# SCH.net
KiCad netlist of a schematic drawn in Altium Designer
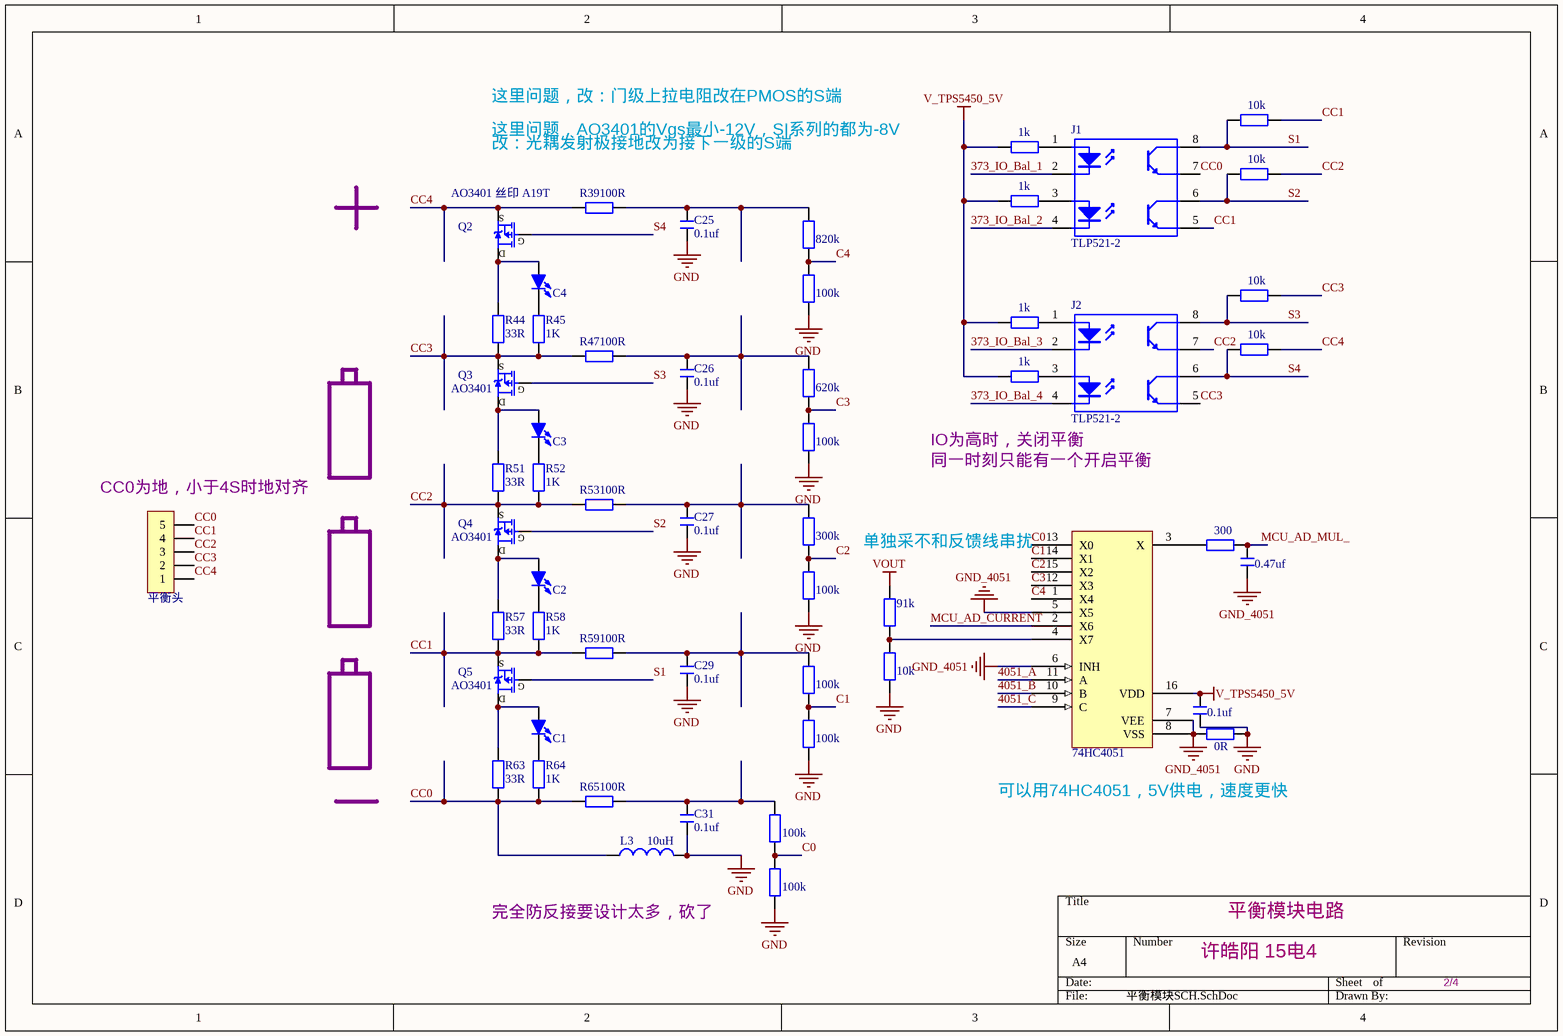
[diagram p0: 平衡模块SCH.SchDoc]

(export (version "E")
  (design (tool "Eeschema 10.0.6"))
  (components
    (comp (ref "*1") (value "74HC4051") (footprint "SOP16_N") (libsource (lib "IC_temp") (part "CD4051")))
    (comp (ref "11")
      (value "91k")
      (footprint "R 0805_M")
      (description "贴片电阻")
      (libsource (lib "3.1   - 电阻-电容-电感") (part "R"))
    )
    (comp (ref "12")
      (value "10k")
      (footprint "R 0805_M")
      (description "贴片电阻")
      (libsource (lib "3.1   - 电阻-电容-电感") (part "R"))
    )
    (comp (ref "C25")
      (value "0.1uf")
      (footprint "C 0805_M")
      (description "无极性贴片电容")
      (libsource (lib "3.1   - 电阻-电容-电感") (part "C"))
    )
    (comp (ref "C26")
      (value "0.1uf")
      (footprint "C 0805_M")
      (description "无极性贴片电容")
      (libsource (lib "3.1   - 电阻-电容-电感") (part "C"))
    )
    (comp (ref "C27")
      (value "0.1uf")
      (footprint "C 0805_M")
      (description "无极性贴片电容")
      (libsource (lib "3.1   - 电阻-电容-电感") (part "C"))
    )
    (comp (ref "C28")
      (value "0.47uf")
      (footprint "C 0805_M")
      (description "无极性贴片电容")
      (libsource (lib "3.1   - 电阻-电容-电感") (part "C"))
    )
    (comp (ref "C29")
      (value "0.1uf")
      (footprint "C 0805_M")
      (description "无极性贴片电容")
      (libsource (lib "3.1   - 电阻-电容-电感") (part "C"))
    )
    (comp (ref "C30")
      (value "0.1uf")
      (footprint "C 0805_M")
      (description "无极性贴片电容")
      (libsource (lib "3.1   - 电阻-电容-电感") (part "C"))
    )
    (comp (ref "C31")
      (value "0.1uf")
      (footprint "C 0805_M")
      (description "无极性贴片电容")
      (libsource (lib "3.1   - 电阻-电容-电感") (part "C"))
    )
    (comp (ref "J1")
      (value "TLP521-2")
      (footprint "SOP8-W2.54_N")
      (description "2路开关光耦")
      (libsource (lib "11.1 - 传感元件") (part "TLP521-2"))
    )
    (comp (ref "J2")
      (value "TLP521-2")
      (footprint "SOP8-W2.54_N")
      (description "2路开关光耦")
      (libsource (lib "11.1 - 传感元件") (part "TLP521-2"))
    )
    (comp (ref "JP9")
      (value "平衡头")
      (footprint "XH2.54-WI-5P")
      (description "5P接插件")
      (libsource (lib "4.6   - 接插件-脚距2.54") (part "Header 5"))
    )
    (comp (ref "L3")
      (value "10uH")
      (footprint "L 0805_M")
      (description "小功率贴片电感")
      (libsource (lib "3.1   - 电阻-电容-电感") (part "L"))
    )
    (comp (ref "LED2")
      (value "C4")
      (footprint "LED 0805G")
      (description "贴片LED")
      (libsource (lib "9.1   - LED") (part "LED-SMD"))
    )
    (comp (ref "LED3")
      (value "C3")
      (footprint "LED 0805G")
      (description "贴片LED")
      (libsource (lib "9.1   - LED") (part "LED-SMD"))
    )
    (comp (ref "LED4")
      (value "C2")
      (footprint "LED 0805G")
      (description "贴片LED")
      (libsource (lib "9.1   - LED") (part "LED-SMD"))
    )
    (comp (ref "LED5")
      (value "C1")
      (footprint "LED 0805G")
      (description "贴片LED")
      (libsource (lib "9.1   - LED") (part "LED-SMD"))
    )
    (comp (ref "Q2")
      (value "AO3401 丝印 A19T")
      (footprint "SOT23-3N")
      (description "P沟道 20V/2.8A")
      (libsource (lib "6.1   - 场效应管-可控硅") (part "SI2301"))
    )
    (comp (ref "Q3")
      (value "AO3401")
      (footprint "SOT23-3N")
      (description "P沟道 20V/2.8A")
      (libsource (lib "6.1   - 场效应管-可控硅") (part "SI2301"))
    )
    (comp (ref "Q4")
      (value "AO3401")
      (footprint "SOT23-3N")
      (description "P沟道 20V/2.8A")
      (libsource (lib "6.1   - 场效应管-可控硅") (part "SI2301"))
    )
    (comp (ref "Q5")
      (value "AO3401")
      (footprint "SOT23-3N")
      (description "P沟道 20V/2.8A")
      (libsource (lib "6.1   - 场效应管-可控硅") (part "SI2301"))
    )
    (comp (ref "R35")
      (value "10k")
      (footprint "R 0805_M")
      (description "贴片电阻")
      (libsource (lib "3.1   - 电阻-电容-电感") (part "R"))
    )
    (comp (ref "R36")
      (value "1k")
      (footprint "R 0805_M")
      (description "贴片电阻")
      (libsource (lib "3.1   - 电阻-电容-电感") (part "R"))
    )
    (comp (ref "R37")
      (value "10k")
      (footprint "R 0805_M")
      (description "贴片电阻")
      (libsource (lib "3.1   - 电阻-电容-电感") (part "R"))
    )
    (comp (ref "R38")
      (value "1k")
      (footprint "R 0805_M")
      (description "贴片电阻")
      (libsource (lib "3.1   - 电阻-电容-电感") (part "R"))
    )
    (comp (ref "R39")
      (value "100R")
      (footprint "R 0805_M")
      (description "贴片电阻")
      (libsource (lib "3.1   - 电阻-电容-电感") (part "R"))
    )
    (comp (ref "R40")
      (value "820k")
      (footprint "R 0805_M")
      (description "贴片电阻")
      (libsource (lib "3.1   - 电阻-电容-电感") (part "R"))
    )
    (comp (ref "R41")
      (value "100k")
      (footprint "R 0805_M")
      (description "贴片电阻")
      (libsource (lib "3.1   - 电阻-电容-电感") (part "R"))
    )
    (comp (ref "R42")
      (value "10k")
      (footprint "R 0805_M")
      (description "贴片电阻")
      (libsource (lib "3.1   - 电阻-电容-电感") (part "R"))
    )
    (comp (ref "R43")
      (value "1k")
      (footprint "R 0805_M")
      (description "贴片电阻")
      (libsource (lib "3.1   - 电阻-电容-电感") (part "R"))
    )
    (comp (ref "R44")
      (value "33R")
      (footprint "R 2512_L")
      (description "贴片电阻")
      (libsource (lib "3.1   - 电阻-电容-电感") (part "R"))
    )
    (comp (ref "R45")
      (value "1K")
      (footprint "R 0805_L")
      (description "贴片电阻")
      (libsource (lib "3.1   - 电阻-电容-电感") (part "R"))
    )
    (comp (ref "R46")
      (value "10k")
      (footprint "R 0805_M")
      (description "贴片电阻")
      (libsource (lib "3.1   - 电阻-电容-电感") (part "R"))
    )
    (comp (ref "R47")
      (value "100R")
      (footprint "R 0805_M")
      (description "贴片电阻")
      (libsource (lib "3.1   - 电阻-电容-电感") (part "R"))
    )
    (comp (ref "R48")
      (value "1k")
      (footprint "R 0805_M")
      (description "贴片电阻")
      (libsource (lib "3.1   - 电阻-电容-电感") (part "R"))
    )
    (comp (ref "R49")
      (value "620k")
      (footprint "R 0805_M")
      (description "贴片电阻")
      (libsource (lib "3.1   - 电阻-电容-电感") (part "R"))
    )
    (comp (ref "R50")
      (value "100k")
      (footprint "R 0805_M")
      (description "贴片电阻")
      (libsource (lib "3.1   - 电阻-电容-电感") (part "R"))
    )
    (comp (ref "R51")
      (value "33R")
      (footprint "R 2512_L")
      (description "贴片电阻")
      (libsource (lib "3.1   - 电阻-电容-电感") (part "R"))
    )
    (comp (ref "R52")
      (value "1K")
      (footprint "R 0805_L")
      (description "贴片电阻")
      (libsource (lib "3.1   - 电阻-电容-电感") (part "R"))
    )
    (comp (ref "R53")
      (value "100R")
      (footprint "R 0805_M")
      (description "贴片电阻")
      (libsource (lib "3.1   - 电阻-电容-电感") (part "R"))
    )
    (comp (ref "R54")
      (value "300k")
      (footprint "R 0805_M")
      (description "贴片电阻")
      (libsource (lib "3.1   - 电阻-电容-电感") (part "R"))
    )
    (comp (ref "R55")
      (value "300")
      (footprint "R 0805_M")
      (description "贴片电阻")
      (libsource (lib "3.1   - 电阻-电容-电感") (part "R"))
    )
    (comp (ref "R56")
      (value "100k")
      (footprint "R 0805_M")
      (description "贴片电阻")
      (libsource (lib "3.1   - 电阻-电容-电感") (part "R"))
    )
    (comp (ref "R57")
      (value "33R")
      (footprint "R 2512_L")
      (description "贴片电阻")
      (libsource (lib "3.1   - 电阻-电容-电感") (part "R"))
    )
    (comp (ref "R58")
      (value "1K")
      (footprint "R 0805_L")
      (description "贴片电阻")
      (libsource (lib "3.1   - 电阻-电容-电感") (part "R"))
    )
    (comp (ref "R59")
      (value "100R")
      (footprint "R 0805_M")
      (description "贴片电阻")
      (libsource (lib "3.1   - 电阻-电容-电感") (part "R"))
    )
    (comp (ref "R60")
      (value "100k")
      (footprint "R 0805_M")
      (description "贴片电阻")
      (libsource (lib "3.1   - 电阻-电容-电感") (part "R"))
    )
    (comp (ref "R61")
      (value "0R")
      (footprint "R 0805_M")
      (description "贴片电阻")
      (libsource (lib "3.1   - 电阻-电容-电感") (part "R"))
    )
    (comp (ref "R62")
      (value "100k")
      (footprint "R 0805_M")
      (description "贴片电阻")
      (libsource (lib "3.1   - 电阻-电容-电感") (part "R"))
    )
    (comp (ref "R63")
      (value "33R")
      (footprint "R 2512_L")
      (description "贴片电阻")
      (libsource (lib "3.1   - 电阻-电容-电感") (part "R"))
    )
    (comp (ref "R64")
      (value "1K")
      (footprint "R 0805_L")
      (description "贴片电阻")
      (libsource (lib "3.1   - 电阻-电容-电感") (part "R"))
    )
    (comp (ref "R65")
      (value "100R")
      (footprint "R 0805_M")
      (description "贴片电阻")
      (libsource (lib "3.1   - 电阻-电容-电感") (part "R"))
    )
    (comp (ref "R66")
      (value "100k")
      (footprint "R 0805_M")
      (description "贴片电阻")
      (libsource (lib "3.1   - 电阻-电容-电感") (part "R"))
    )
    (comp (ref "R67")
      (value "100k")
      (footprint "R 0805_M")
      (description "贴片电阻")
      (libsource (lib "3.1   - 电阻-电容-电感") (part "R"))
    )
  )
  (nets
    (net (code "1") (name "/373_IO_Bal_1") (class "Default")
      (node (ref "J1") (pin "2") (pinfunction "1K_2") (pintype "passive"))
    )
    (net (code "2") (name "/373_IO_Bal_2") (class "Default")
      (node (ref "J1") (pin "4") (pinfunction "2K_4") (pintype "passive"))
    )
    (net (code "3") (name "/373_IO_Bal_3") (class "Default")
      (node (ref "J2") (pin "2") (pinfunction "1K_2") (pintype "passive"))
    )
    (net (code "4") (name "/373_IO_Bal_4") (class "Default")
      (node (ref "J2") (pin "4") (pinfunction "2K_4") (pintype "passive"))
    )
    (net (code "5") (name "/4051_A") (class "Default")
      (node (ref "*1") (pin "11") (pinfunction "A_11") (pintype "input"))
    )
    (net (code "6") (name "/4051_B") (class "Default")
      (node (ref "*1") (pin "10") (pinfunction "B_10") (pintype "input"))
    )
    (net (code "7") (name "/4051_C") (class "Default")
      (node (ref "*1") (pin "9") (pinfunction "C_9") (pintype "input"))
    )
    (net (code "8") (name "/C0") (class "Default")
      (node (ref "*1") (pin "13") (pinfunction "X0_13") (pintype "passive"))
      (node (ref "R66") (pin "2") (pinfunction "2_2") (pintype "passive"))
      (node (ref "R67") (pin "1") (pinfunction "1_1") (pintype "passive"))
    )
    (net (code "9") (name "/C1") (class "Default")
      (node (ref "*1") (pin "14") (pinfunction "X1_14") (pintype "passive"))
      (node (ref "R60") (pin "2") (pinfunction "2_2") (pintype "passive"))
      (node (ref "R62") (pin "1") (pinfunction "1_1") (pintype "passive"))
    )
    (net (code "10") (name "/C2") (class "Default")
      (node (ref "*1") (pin "15") (pinfunction "X2_15") (pintype "passive"))
      (node (ref "R54") (pin "2") (pinfunction "2_2") (pintype "passive"))
      (node (ref "R56") (pin "1") (pinfunction "1_1") (pintype "passive"))
    )
    (net (code "11") (name "/C3") (class "Default")
      (node (ref "*1") (pin "12") (pinfunction "X3_12") (pintype "passive"))
      (node (ref "R49") (pin "2") (pinfunction "2_2") (pintype "passive"))
      (node (ref "R50") (pin "1") (pinfunction "1_1") (pintype "passive"))
    )
    (net (code "12") (name "/C4") (class "Default")
      (node (ref "*1") (pin "1") (pinfunction "X4_1") (pintype "passive"))
      (node (ref "R40") (pin "2") (pinfunction "2_2") (pintype "passive"))
      (node (ref "R41") (pin "1") (pinfunction "1_1") (pintype "passive"))
    )
    (net (code "13") (name "/CC0") (class "Default")
      (node (ref "J1") (pin "7") (pinfunction "1E_7") (pintype "passive"))
      (node (ref "JP9") (pin "5") (pinfunction "5_5") (pintype "passive"))
      (node (ref "L3") (pin "1") (pinfunction "1_1") (pintype "passive"))
      (node (ref "R63") (pin "1") (pinfunction "1_1") (pintype "passive"))
      (node (ref "R64") (pin "2") (pinfunction "2_2") (pintype "passive"))
      (node (ref "R65") (pin "2") (pinfunction "2_2") (pintype "passive"))
    )
    (net (code "14") (name "/CC1") (class "Default")
      (node (ref "J1") (pin "5") (pinfunction "2E_5") (pintype "passive"))
      (node (ref "JP9") (pin "4") (pinfunction "4_4") (pintype "passive"))
      (node (ref "Q5") (pin "2") (pinfunction "S_2") (pintype "passive"))
      (node (ref "R35") (pin "2") (pinfunction "2_2") (pintype "passive"))
      (node (ref "R57") (pin "1") (pinfunction "1_1") (pintype "passive"))
      (node (ref "R58") (pin "2") (pinfunction "2_2") (pintype "passive"))
      (node (ref "R59") (pin "2") (pinfunction "2_2") (pintype "passive"))
    )
    (net (code "15") (name "/CC2") (class "Default")
      (node (ref "J2") (pin "7") (pinfunction "1E_7") (pintype "passive"))
      (node (ref "JP9") (pin "3") (pinfunction "3_3") (pintype "passive"))
      (node (ref "Q4") (pin "2") (pinfunction "S_2") (pintype "passive"))
      (node (ref "R37") (pin "2") (pinfunction "2_2") (pintype "passive"))
      (node (ref "R51") (pin "1") (pinfunction "1_1") (pintype "passive"))
      (node (ref "R52") (pin "2") (pinfunction "2_2") (pintype "passive"))
      (node (ref "R53") (pin "2") (pinfunction "2_2") (pintype "passive"))
    )
    (net (code "16") (name "/CC3") (class "Default")
      (node (ref "J2") (pin "5") (pinfunction "2E_5") (pintype "passive"))
      (node (ref "JP9") (pin "2") (pinfunction "2_2") (pintype "passive"))
      (node (ref "Q3") (pin "2") (pinfunction "S_2") (pintype "passive"))
      (node (ref "R42") (pin "2") (pinfunction "2_2") (pintype "passive"))
      (node (ref "R44") (pin "1") (pinfunction "1_1") (pintype "passive"))
      (node (ref "R45") (pin "2") (pinfunction "2_2") (pintype "passive"))
      (node (ref "R47") (pin "2") (pinfunction "2_2") (pintype "passive"))
    )
    (net (code "17") (name "/CC4") (class "Default")
      (node (ref "JP9") (pin "1") (pinfunction "1_1") (pintype "passive"))
      (node (ref "Q2") (pin "2") (pinfunction "S_2") (pintype "passive"))
      (node (ref "R39") (pin "2") (pinfunction "2_2") (pintype "passive"))
      (node (ref "R46") (pin "2") (pinfunction "2_2") (pintype "passive"))
    )
    (net (code "18") (name "/MCU_AD_CURRENT") (class "Default")
      (node (ref "*1") (pin "2") (pinfunction "X6_2") (pintype "passive"))
    )
    (net (code "19") (name "/MCU_AD_MUL_") (class "Default")
      (node (ref "C28") (pin "2") (pinfunction "2_2") (pintype "passive"))
      (node (ref "R55") (pin "1") (pinfunction "1_1") (pintype "passive"))
    )
    (net (code "20") (name "/S1") (class "Default")
      (node (ref "J1") (pin "8") (pinfunction "1C_8") (pintype "passive"))
      (node (ref "Q5") (pin "1") (pinfunction "G_1") (pintype "passive"))
      (node (ref "R35") (pin "1") (pinfunction "1_1") (pintype "passive"))
    )
    (net (code "21") (name "/S2") (class "Default")
      (node (ref "J1") (pin "6") (pinfunction "2C_6") (pintype "passive"))
      (node (ref "Q4") (pin "1") (pinfunction "G_1") (pintype "passive"))
      (node (ref "R37") (pin "1") (pinfunction "1_1") (pintype "passive"))
    )
    (net (code "22") (name "/S3") (class "Default")
      (node (ref "J2") (pin "8") (pinfunction "1C_8") (pintype "passive"))
      (node (ref "Q3") (pin "1") (pinfunction "G_1") (pintype "passive"))
      (node (ref "R42") (pin "1") (pinfunction "1_1") (pintype "passive"))
    )
    (net (code "23") (name "/S4") (class "Default")
      (node (ref "J2") (pin "6") (pinfunction "2C_6") (pintype "passive"))
      (node (ref "Q2") (pin "1") (pinfunction "G_1") (pintype "passive"))
      (node (ref "R46") (pin "1") (pinfunction "1_1") (pintype "passive"))
    )
    (net (code "24") (name "GND") (class "Default")
      (node (ref "12") (pin "2") (pinfunction "2_2") (pintype "passive"))
      (node (ref "C25") (pin "1") (pinfunction "1_1") (pintype "passive"))
      (node (ref "C26") (pin "1") (pinfunction "1_1") (pintype "passive"))
      (node (ref "C27") (pin "1") (pinfunction "1_1") (pintype "passive"))
      (node (ref "C29") (pin "1") (pinfunction "1_1") (pintype "passive"))
      (node (ref "C30") (pin "1") (pinfunction "1_1") (pintype "passive"))
      (node (ref "C31") (pin "1") (pinfunction "1_1") (pintype "passive"))
      (node (ref "L3") (pin "2") (pinfunction "2_2") (pintype "passive"))
      (node (ref "R41") (pin "2") (pinfunction "2_2") (pintype "passive"))
      (node (ref "R50") (pin "2") (pinfunction "2_2") (pintype "passive"))
      (node (ref "R56") (pin "2") (pinfunction "2_2") (pintype "passive"))
      (node (ref "R61") (pin "1") (pinfunction "1_1") (pintype "passive"))
      (node (ref "R62") (pin "2") (pinfunction "2_2") (pintype "passive"))
      (node (ref "R67") (pin "2") (pinfunction "2_2") (pintype "passive"))
    )
    (net (code "25") (name "GND_4051") (class "Default")
      (node (ref "*1") (pin "5") (pinfunction "X5_5") (pintype "passive"))
      (node (ref "*1") (pin "6") (pinfunction "INH_6") (pintype "input"))
      (node (ref "*1") (pin "7") (pinfunction "VEE_7") (pintype "passive"))
      (node (ref "*1") (pin "8") (pinfunction "VSS_8") (pintype "power_in"))
      (node (ref "C28") (pin "1") (pinfunction "1_1") (pintype "passive"))
      (node (ref "R61") (pin "2") (pinfunction "2_2") (pintype "passive"))
    )
    (net (code "26") (name "Net-(*1-X)") (class "Default")
      (node (ref "*1") (pin "3") (pinfunction "X_3") (pintype "passive"))
      (node (ref "R55") (pin "2") (pinfunction "2_2") (pintype "passive"))
    )
    (net (code "27") (name "Net-(*1-X7)") (class "Default")
      (node (ref "*1") (pin "4") (pinfunction "X7_4") (pintype "passive"))
      (node (ref "11") (pin "2") (pinfunction "2_2") (pintype "passive"))
      (node (ref "12") (pin "1") (pinfunction "1_1") (pintype "passive"))
    )
    (net (code "28") (name "Net-(C25-Pad2)") (class "Default")
      (node (ref "C25") (pin "2") (pinfunction "2_2") (pintype "passive"))
      (node (ref "R39") (pin "1") (pinfunction "1_1") (pintype "passive"))
      (node (ref "R40") (pin "1") (pinfunction "1_1") (pintype "passive"))
    )
    (net (code "29") (name "Net-(C26-Pad2)") (class "Default")
      (node (ref "C26") (pin "2") (pinfunction "2_2") (pintype "passive"))
      (node (ref "R47") (pin "1") (pinfunction "1_1") (pintype "passive"))
      (node (ref "R49") (pin "1") (pinfunction "1_1") (pintype "passive"))
    )
    (net (code "30") (name "Net-(C27-Pad2)") (class "Default")
      (node (ref "C27") (pin "2") (pinfunction "2_2") (pintype "passive"))
      (node (ref "R53") (pin "1") (pinfunction "1_1") (pintype "passive"))
      (node (ref "R54") (pin "1") (pinfunction "1_1") (pintype "passive"))
    )
    (net (code "31") (name "Net-(C29-Pad2)") (class "Default")
      (node (ref "C29") (pin "2") (pinfunction "2_2") (pintype "passive"))
      (node (ref "R59") (pin "1") (pinfunction "1_1") (pintype "passive"))
      (node (ref "R60") (pin "1") (pinfunction "1_1") (pintype "passive"))
    )
    (net (code "32") (name "Net-(C31-Pad2)") (class "Default")
      (node (ref "C31") (pin "2") (pinfunction "2_2") (pintype "passive"))
      (node (ref "R65") (pin "1") (pinfunction "1_1") (pintype "passive"))
      (node (ref "R66") (pin "1") (pinfunction "1_1") (pintype "passive"))
    )
    (net (code "33") (name "Net-(J1-1A)") (class "Default")
      (node (ref "J1") (pin "1") (pinfunction "1A_1") (pintype "passive"))
      (node (ref "R36") (pin "1") (pinfunction "1_1") (pintype "passive"))
    )
    (net (code "34") (name "Net-(J1-2A)") (class "Default")
      (node (ref "J1") (pin "3") (pinfunction "2A_3") (pintype "passive"))
      (node (ref "R38") (pin "1") (pinfunction "1_1") (pintype "passive"))
    )
    (net (code "35") (name "Net-(J2-1A)") (class "Default")
      (node (ref "J2") (pin "1") (pinfunction "1A_1") (pintype "passive"))
      (node (ref "R43") (pin "1") (pinfunction "1_1") (pintype "passive"))
    )
    (net (code "36") (name "Net-(J2-2A)") (class "Default")
      (node (ref "J2") (pin "3") (pinfunction "2A_3") (pintype "passive"))
      (node (ref "R48") (pin "1") (pinfunction "1_1") (pintype "passive"))
    )
    (net (code "37") (name "Net-(LED2-A)") (class "Default")
      (node (ref "LED2") (pin "1") (pinfunction "A_1") (pintype "passive"))
      (node (ref "Q2") (pin "3") (pinfunction "D_3") (pintype "passive"))
      (node (ref "R44") (pin "2") (pinfunction "2_2") (pintype "passive"))
    )
    (net (code "38") (name "Net-(LED2-K)") (class "Default")
      (node (ref "LED2") (pin "2") (pinfunction "K_2") (pintype "passive"))
      (node (ref "R45") (pin "1") (pinfunction "1_1") (pintype "passive"))
    )
    (net (code "39") (name "Net-(LED3-A)") (class "Default")
      (node (ref "LED3") (pin "1") (pinfunction "A_1") (pintype "passive"))
      (node (ref "Q3") (pin "3") (pinfunction "D_3") (pintype "passive"))
      (node (ref "R51") (pin "2") (pinfunction "2_2") (pintype "passive"))
    )
    (net (code "40") (name "Net-(LED3-K)") (class "Default")
      (node (ref "LED3") (pin "2") (pinfunction "K_2") (pintype "passive"))
      (node (ref "R52") (pin "1") (pinfunction "1_1") (pintype "passive"))
    )
    (net (code "41") (name "Net-(LED4-A)") (class "Default")
      (node (ref "LED4") (pin "1") (pinfunction "A_1") (pintype "passive"))
      (node (ref "Q4") (pin "3") (pinfunction "D_3") (pintype "passive"))
      (node (ref "R57") (pin "2") (pinfunction "2_2") (pintype "passive"))
    )
    (net (code "42") (name "Net-(LED4-K)") (class "Default")
      (node (ref "LED4") (pin "2") (pinfunction "K_2") (pintype "passive"))
      (node (ref "R58") (pin "1") (pinfunction "1_1") (pintype "passive"))
    )
    (net (code "43") (name "Net-(LED5-A)") (class "Default")
      (node (ref "LED5") (pin "1") (pinfunction "A_1") (pintype "passive"))
      (node (ref "Q5") (pin "3") (pinfunction "D_3") (pintype "passive"))
      (node (ref "R63") (pin "2") (pinfunction "2_2") (pintype "passive"))
    )
    (net (code "44") (name "Net-(LED5-K)") (class "Default")
      (node (ref "LED5") (pin "2") (pinfunction "K_2") (pintype "passive"))
      (node (ref "R64") (pin "1") (pinfunction "1_1") (pintype "passive"))
    )
    (net (code "45") (name "VOUT") (class "Default")
      (node (ref "11") (pin "1") (pinfunction "1_1") (pintype "passive"))
    )
    (net (code "46") (name "V_TPS5450_5V") (class "Default")
      (node (ref "*1") (pin "16") (pinfunction "VDD_16") (pintype "power_in"))
      (node (ref "C30") (pin "2") (pinfunction "2_2") (pintype "passive"))
      (node (ref "R36") (pin "2") (pinfunction "2_2") (pintype "passive"))
      (node (ref "R38") (pin "2") (pinfunction "2_2") (pintype "passive"))
      (node (ref "R43") (pin "2") (pinfunction "2_2") (pintype "passive"))
      (node (ref "R48") (pin "2") (pinfunction "2_2") (pintype "passive"))
    )
  )
)
